# Sync_Out.net
KiCad netlist of a schematic drawn in Altium Designer
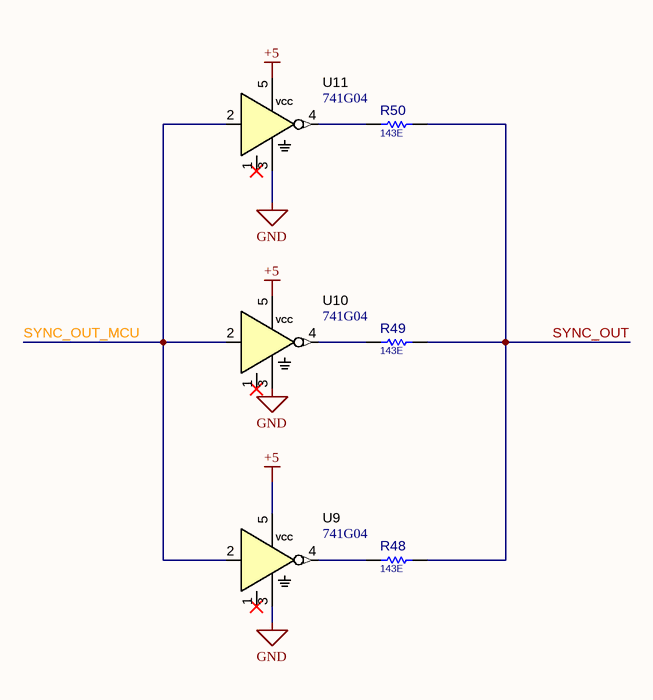
[diagram p0: Sync Out.SchDoc]

(export (version "E")
  (design (tool "Eeschema 10.0.6"))
  (components
    (comp (ref "R48")
      (value "143E")
      (footprint "R0603")
      (description "RESISTOR, SMD")
      (libsource (lib "passive_smd") (part "RES_SMD_0603"))
    )
    (comp (ref "R49")
      (value "143E")
      (footprint "R0603")
      (description "RESISTOR, SMD")
      (libsource (lib "passive_smd") (part "RES_SMD_0603"))
    )
    (comp (ref "R50")
      (value "143E")
      (footprint "R0603")
      (description "RESISTOR, SMD")
      (libsource (lib "passive_smd") (part "RES_SMD_0603"))
    )
    (comp (ref "U9")
      (value "741G04")
      (footprint "SOT353_5")
      (description "GATE, NOT, SINGLE, SOT353 SMD")
      (fields (field (name "MANF") "Texas Instruments") (field (name "MANF_P#") "SN74LVC1GU04DCK"))
      (libsource (lib "logic_gate") (part "NOT_SN74LVC1G04_SOT353"))
    )
    (comp (ref "U10")
      (value "741G04")
      (footprint "SOT353_5")
      (description "GATE, NOT, SINGLE, SOT353 SMD")
      (fields (field (name "MANF") "Texas Instruments") (field (name "MANF_P#") "SN74LVC1GU04DCK"))
      (libsource (lib "logic_gate") (part "NOT_SN74LVC1G04_SOT353"))
    )
    (comp (ref "U11")
      (value "741G04")
      (footprint "SOT353_5")
      (description "GATE, NOT, SINGLE, SOT353 SMD")
      (fields (field (name "MANF") "Texas Instruments") (field (name "MANF_P#") "SN74LVC1GU04DCK"))
      (libsource (lib "logic_gate") (part "NOT_SN74LVC1G04_SOT353"))
    )
  )
  (nets
    (net (code "1") (name "+5") (class "Default")
      (node (ref "U10") (pin "5") (pinfunction "VCC_5") (pintype "power_in"))
      (node (ref "U11") (pin "5") (pinfunction "VCC_5") (pintype "power_in"))
      (node (ref "U9") (pin "5") (pinfunction "VCC_5") (pintype "power_in"))
    )
    (net (code "2") (name "/SYNC_OUT") (class "Default")
      (node (ref "R48") (pin "2") (pinfunction "2_2") (pintype "passive"))
      (node (ref "R49") (pin "2") (pinfunction "2_2") (pintype "passive"))
      (node (ref "R50") (pin "2") (pinfunction "2_2") (pintype "passive"))
    )
    (net (code "3") (name "/SYNC_OUT_MCU") (class "Default")
      (node (ref "U10") (pin "2") (pinfunction "A_2") (pintype "passive"))
      (node (ref "U11") (pin "2") (pinfunction "A_2") (pintype "passive"))
      (node (ref "U9") (pin "2") (pinfunction "A_2") (pintype "passive"))
    )
    (net (code "4") (name "GND") (class "Default")
      (node (ref "U10") (pin "3") (pinfunction "GND_3") (pintype "power_in"))
      (node (ref "U11") (pin "3") (pinfunction "GND_3") (pintype "power_in"))
      (node (ref "U9") (pin "3") (pinfunction "GND_3") (pintype "power_in"))
    )
    (net (code "5") (name "Net-(U9-Y)") (class "Default")
      (node (ref "R48") (pin "1") (pinfunction "1_1") (pintype "passive"))
      (node (ref "U9") (pin "4") (pinfunction "Y_4") (pintype "output"))
    )
    (net (code "6") (name "Net-(U10-Y)") (class "Default")
      (node (ref "R49") (pin "1") (pinfunction "1_1") (pintype "passive"))
      (node (ref "U10") (pin "4") (pinfunction "Y_4") (pintype "output"))
    )
    (net (code "7") (name "Net-(U11-Y)") (class "Default")
      (node (ref "R50") (pin "1") (pinfunction "1_1") (pintype "passive"))
      (node (ref "U11") (pin "4") (pinfunction "Y_4") (pintype "output"))
    )
    (net (code "8") (name "unconnected-(U9-NC-Pad1)") (class "Default")
      (node (ref "U9") (pin "1") (pinfunction "NC_1") (pintype "passive+no_connect"))
    )
    (net (code "9") (name "unconnected-(U10-NC-Pad1)") (class "Default")
      (node (ref "U10") (pin "1") (pinfunction "NC_1") (pintype "passive+no_connect"))
    )
    (net (code "10") (name "unconnected-(U11-NC-Pad1)") (class "Default")
      (node (ref "U11") (pin "1") (pinfunction "NC_1") (pintype "passive+no_connect"))
    )
  )
)
